# mainboard_v1.net
KiCad netlist of a schematic drawn in EAGLE
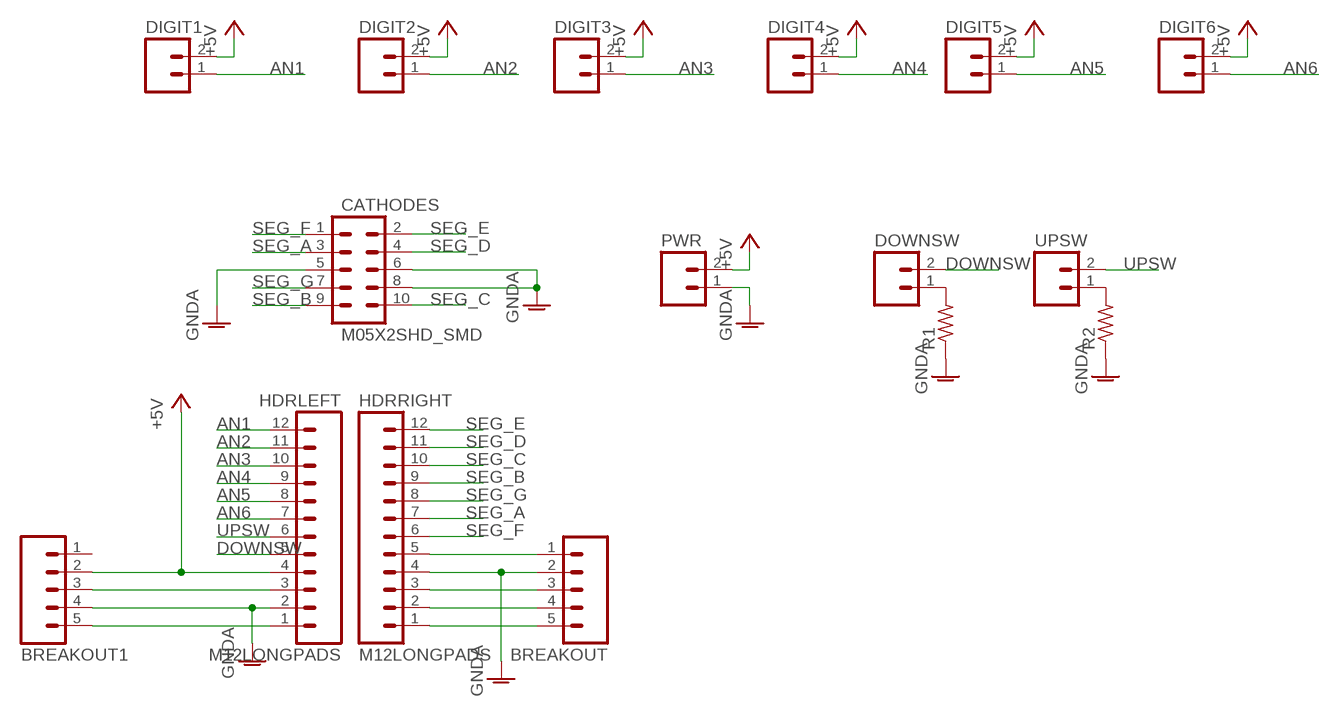
[diagram p0: schematic, sheet 1]

(export (version "E")
  (design (tool "Eeschema 10.0.6"))
  (components
    (comp (ref "BREAKOUT")
      (value "M05")
      (footprint "eagle-import:05P")
      (libsource (lib "eagle-import") (part "M05"))
    )
    (comp (ref "BREAKOUT1")
      (value "M05")
      (footprint "eagle-import:05P")
      (libsource (lib "eagle-import") (part "M05"))
    )
    (comp (ref "CATHODES")
      (value "M05X2SHD_SMD")
      (footprint "eagle-import:2X5-SHROUDED_SMD")
      (libsource (lib "eagle-import") (part "M05X2SHD_SMD"))
    )
    (comp (ref "DIGIT1")
      (value "M02")
      (footprint "eagle-import:02P")
      (libsource (lib "eagle-import") (part "M02"))
    )
    (comp (ref "DIGIT2")
      (value "M02")
      (footprint "eagle-import:02P")
      (libsource (lib "eagle-import") (part "M02"))
    )
    (comp (ref "DIGIT3")
      (value "M02")
      (footprint "eagle-import:02P")
      (libsource (lib "eagle-import") (part "M02"))
    )
    (comp (ref "DIGIT4")
      (value "M02")
      (footprint "eagle-import:02P")
      (libsource (lib "eagle-import") (part "M02"))
    )
    (comp (ref "DIGIT5")
      (value "M02")
      (footprint "eagle-import:02P")
      (libsource (lib "eagle-import") (part "M02"))
    )
    (comp (ref "DIGIT6")
      (value "M02")
      (footprint "eagle-import:02P")
      (libsource (lib "eagle-import") (part "M02"))
    )
    (comp (ref "DOWNSW")
      (value "M02")
      (footprint "eagle-import:02P")
      (libsource (lib "eagle-import") (part "M02"))
    )
    (comp (ref "HDRLEFT")
      (value "M12LONGPADS")
      (footprint "eagle-import:1X12_LONGPADS")
      (libsource (lib "eagle-import") (part "M12LONGPADS"))
    )
    (comp (ref "HDRRIGHT")
      (value "M12LONGPADS")
      (footprint "eagle-import:1X12_LONGPADS")
      (libsource (lib "eagle-import") (part "M12LONGPADS"))
    )
    (comp (ref "PWR")
      (value "M02")
      (footprint "eagle-import:02P")
      (libsource (lib "eagle-import") (part "M02"))
    )
    (comp (ref "R1")
      (value "R-US_M0805")
      (footprint "eagle-import:M0805")
      (libsource (lib "eagle-import") (part "R-US_M0805"))
    )
    (comp (ref "R2")
      (value "R-US_M0805")
      (footprint "eagle-import:M0805")
      (libsource (lib "eagle-import") (part "R-US_M0805"))
    )
    (comp (ref "UPSW")
      (value "M02")
      (footprint "eagle-import:02P")
      (libsource (lib "eagle-import") (part "M02"))
    )
  )
  (nets
    (net (code "1") (name "+5V") (class "Default")
      (node (ref "BREAKOUT1") (pin "2") (pinfunction "2_2") (pintype "passive"))
      (node (ref "DIGIT1") (pin "2") (pinfunction "2_2") (pintype "passive"))
      (node (ref "DIGIT2") (pin "2") (pinfunction "2_2") (pintype "passive"))
      (node (ref "DIGIT3") (pin "2") (pinfunction "2_2") (pintype "passive"))
      (node (ref "DIGIT4") (pin "2") (pinfunction "2_2") (pintype "passive"))
      (node (ref "DIGIT5") (pin "2") (pinfunction "2_2") (pintype "passive"))
      (node (ref "DIGIT6") (pin "2") (pinfunction "2_2") (pintype "passive"))
      (node (ref "HDRLEFT") (pin "4") (pinfunction "4_4") (pintype "passive"))
      (node (ref "PWR") (pin "2") (pinfunction "2_2") (pintype "passive"))
    )
    (net (code "2") (name "/AN1") (class "Default")
      (node (ref "DIGIT1") (pin "1") (pinfunction "1_1") (pintype "passive"))
      (node (ref "HDRLEFT") (pin "12") (pinfunction "12_12") (pintype "passive"))
    )
    (net (code "3") (name "/AN2") (class "Default")
      (node (ref "DIGIT2") (pin "1") (pinfunction "1_1") (pintype "passive"))
      (node (ref "HDRLEFT") (pin "11") (pinfunction "11_11") (pintype "passive"))
    )
    (net (code "4") (name "/AN3") (class "Default")
      (node (ref "DIGIT3") (pin "1") (pinfunction "1_1") (pintype "passive"))
      (node (ref "HDRLEFT") (pin "10") (pinfunction "10_10") (pintype "passive"))
    )
    (net (code "5") (name "/AN4") (class "Default")
      (node (ref "DIGIT4") (pin "1") (pinfunction "1_1") (pintype "passive"))
      (node (ref "HDRLEFT") (pin "9") (pinfunction "9_9") (pintype "passive"))
    )
    (net (code "6") (name "/AN5") (class "Default")
      (node (ref "DIGIT5") (pin "1") (pinfunction "1_1") (pintype "passive"))
      (node (ref "HDRLEFT") (pin "8") (pinfunction "8_8") (pintype "passive"))
    )
    (net (code "7") (name "/AN6") (class "Default")
      (node (ref "DIGIT6") (pin "1") (pinfunction "1_1") (pintype "passive"))
      (node (ref "HDRLEFT") (pin "7") (pinfunction "7_7") (pintype "passive"))
    )
    (net (code "8") (name "/DOWNSW") (class "Default")
      (node (ref "DOWNSW") (pin "2") (pinfunction "2_2") (pintype "passive"))
      (node (ref "HDRLEFT") (pin "5") (pinfunction "5_5") (pintype "passive"))
    )
    (net (code "9") (name "/SEG_A") (class "Default")
      (node (ref "CATHODES") (pin "3") (pinfunction "3_3") (pintype "passive"))
      (node (ref "HDRRIGHT") (pin "7") (pinfunction "7_7") (pintype "passive"))
    )
    (net (code "10") (name "/SEG_B") (class "Default")
      (node (ref "CATHODES") (pin "9") (pinfunction "9_9") (pintype "passive"))
      (node (ref "HDRRIGHT") (pin "9") (pinfunction "9_9") (pintype "passive"))
    )
    (net (code "11") (name "/SEG_C") (class "Default")
      (node (ref "CATHODES") (pin "10") (pinfunction "10_10") (pintype "passive"))
      (node (ref "HDRRIGHT") (pin "10") (pinfunction "10_10") (pintype "passive"))
    )
    (net (code "12") (name "/SEG_D") (class "Default")
      (node (ref "CATHODES") (pin "4") (pinfunction "4_4") (pintype "passive"))
      (node (ref "HDRRIGHT") (pin "11") (pinfunction "11_11") (pintype "passive"))
    )
    (net (code "13") (name "/SEG_E") (class "Default")
      (node (ref "CATHODES") (pin "2") (pinfunction "2_2") (pintype "passive"))
      (node (ref "HDRRIGHT") (pin "12") (pinfunction "12_12") (pintype "passive"))
    )
    (net (code "14") (name "/SEG_F") (class "Default")
      (node (ref "CATHODES") (pin "1") (pinfunction "1_1") (pintype "passive"))
      (node (ref "HDRRIGHT") (pin "6") (pinfunction "6_6") (pintype "passive"))
    )
    (net (code "15") (name "/SEG_G") (class "Default")
      (node (ref "CATHODES") (pin "7") (pinfunction "7_7") (pintype "passive"))
      (node (ref "HDRRIGHT") (pin "8") (pinfunction "8_8") (pintype "passive"))
    )
    (net (code "16") (name "/UPSW") (class "Default")
      (node (ref "HDRLEFT") (pin "6") (pinfunction "6_6") (pintype "passive"))
      (node (ref "UPSW") (pin "2") (pinfunction "2_2") (pintype "passive"))
    )
    (net (code "17") (name "GNDA") (class "Default")
      (node (ref "BREAKOUT") (pin "2") (pinfunction "2_2") (pintype "passive"))
      (node (ref "BREAKOUT1") (pin "4") (pinfunction "4_4") (pintype "passive"))
      (node (ref "CATHODES") (pin "5") (pinfunction "5_5") (pintype "passive"))
      (node (ref "CATHODES") (pin "6") (pinfunction "6_6") (pintype "passive"))
      (node (ref "CATHODES") (pin "8") (pinfunction "8_8") (pintype "passive"))
      (node (ref "HDRLEFT") (pin "2") (pinfunction "2_2") (pintype "passive"))
      (node (ref "HDRRIGHT") (pin "4") (pinfunction "4_4") (pintype "passive"))
      (node (ref "PWR") (pin "1") (pinfunction "1_1") (pintype "passive"))
      (node (ref "R1") (pin "1") (pinfunction "1_1") (pintype "passive"))
      (node (ref "R2") (pin "1") (pinfunction "1_1") (pintype "passive"))
    )
    (net (code "18") (name "Net-(BREAKOUT-Pad1)") (class "Default")
      (node (ref "BREAKOUT") (pin "1") (pinfunction "1_1") (pintype "passive"))
      (node (ref "HDRRIGHT") (pin "5") (pinfunction "5_5") (pintype "passive"))
    )
    (net (code "19") (name "Net-(BREAKOUT-Pad3)") (class "Default")
      (node (ref "BREAKOUT") (pin "3") (pinfunction "3_3") (pintype "passive"))
      (node (ref "HDRRIGHT") (pin "3") (pinfunction "3_3") (pintype "passive"))
    )
    (net (code "20") (name "Net-(BREAKOUT-Pad4)") (class "Default")
      (node (ref "BREAKOUT") (pin "4") (pinfunction "4_4") (pintype "passive"))
      (node (ref "HDRRIGHT") (pin "2") (pinfunction "2_2") (pintype "passive"))
    )
    (net (code "21") (name "Net-(BREAKOUT-Pad5)") (class "Default")
      (node (ref "BREAKOUT") (pin "5") (pinfunction "5_5") (pintype "passive"))
      (node (ref "HDRRIGHT") (pin "1") (pinfunction "1_1") (pintype "passive"))
    )
    (net (code "22") (name "Net-(BREAKOUT1-Pad3)") (class "Default")
      (node (ref "BREAKOUT1") (pin "3") (pinfunction "3_3") (pintype "passive"))
      (node (ref "HDRLEFT") (pin "3") (pinfunction "3_3") (pintype "passive"))
    )
    (net (code "23") (name "Net-(BREAKOUT1-Pad5)") (class "Default")
      (node (ref "BREAKOUT1") (pin "5") (pinfunction "5_5") (pintype "passive"))
      (node (ref "HDRLEFT") (pin "1") (pinfunction "1_1") (pintype "passive"))
    )
    (net (code "24") (name "Net-(DOWNSW-Pad1)") (class "Default")
      (node (ref "DOWNSW") (pin "1") (pinfunction "1_1") (pintype "passive"))
      (node (ref "R1") (pin "2") (pinfunction "2_2") (pintype "passive"))
    )
    (net (code "25") (name "Net-(R2-Pad2)") (class "Default")
      (node (ref "R2") (pin "2") (pinfunction "2_2") (pintype "passive"))
      (node (ref "UPSW") (pin "1") (pinfunction "1_1") (pintype "passive"))
    )
    (net (code "26") (name "unconnected-(BREAKOUT1-Pad1)") (class "Default")
      (node (ref "BREAKOUT1") (pin "1") (pinfunction "1_1") (pintype "passive"))
    )
  )
)
